# CNY70.net
KiCad netlist of a schematic drawn in EAGLE
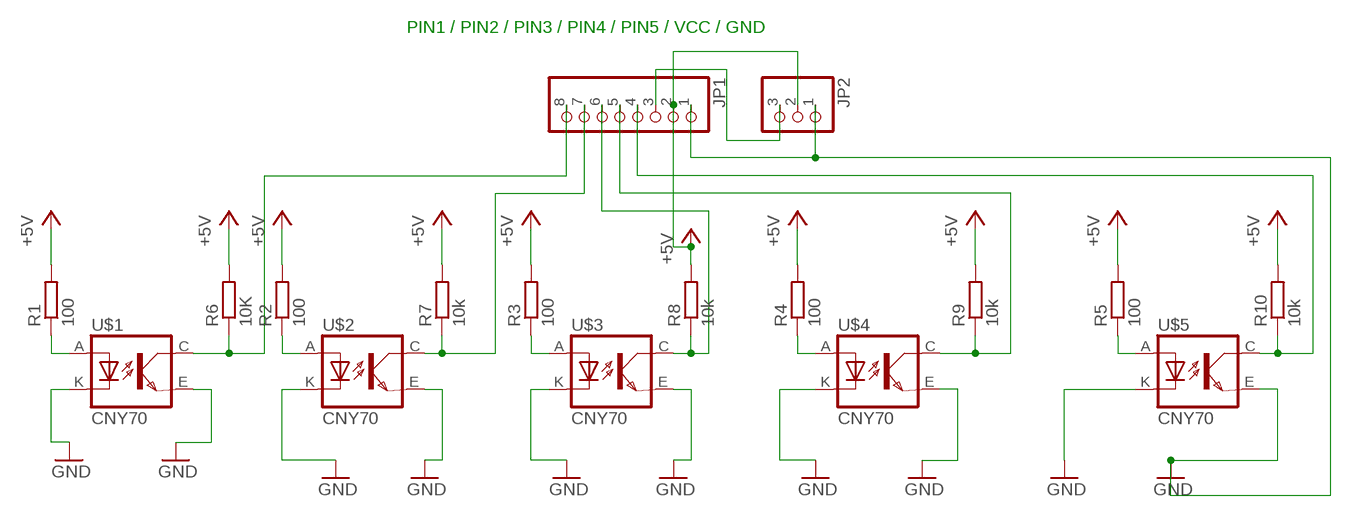
[diagram p0: schematic, sheet 1]

(export (version "E")
  (design (tool "Eeschema 10.0.6"))
  (components
    (comp (ref "JP1")
      (value "PINHD-1X8")
      (footprint "eagle-import:1X08")
      (libsource (lib "eagle-import") (part "PINHD-1X8"))
    )
    (comp (ref "JP2")
      (value "PINHD-1X3")
      (footprint "eagle-import:1X03")
      (libsource (lib "eagle-import") (part "PINHD-1X3"))
    )
    (comp (ref "R1")
      (value "100")
      (footprint "eagle-import:0309_12")
      (libsource (lib "eagle-import") (part "R-EU_0309/12"))
    )
    (comp (ref "R2")
      (value "100")
      (footprint "eagle-import:0309_12")
      (libsource (lib "eagle-import") (part "R-EU_0309/12"))
    )
    (comp (ref "R3")
      (value "100")
      (footprint "eagle-import:0309_12")
      (libsource (lib "eagle-import") (part "R-EU_0309/12"))
    )
    (comp (ref "R4")
      (value "100")
      (footprint "eagle-import:0309_12")
      (libsource (lib "eagle-import") (part "R-EU_0309/12"))
    )
    (comp (ref "R5")
      (value "100")
      (footprint "eagle-import:0309_12")
      (libsource (lib "eagle-import") (part "R-EU_0309/12"))
    )
    (comp (ref "R6")
      (value "10K")
      (footprint "eagle-import:0309_12")
      (libsource (lib "eagle-import") (part "R-EU_0309/12"))
    )
    (comp (ref "R7")
      (value "10k")
      (footprint "eagle-import:0309_12")
      (libsource (lib "eagle-import") (part "R-EU_0309/12"))
    )
    (comp (ref "R8")
      (value "10k")
      (footprint "eagle-import:0309_12")
      (libsource (lib "eagle-import") (part "R-EU_0309/12"))
    )
    (comp (ref "R9")
      (value "10k")
      (footprint "eagle-import:0309_12")
      (libsource (lib "eagle-import") (part "R-EU_0309/12"))
    )
    (comp (ref "R10")
      (value "10k")
      (footprint "eagle-import:0309_12")
      (libsource (lib "eagle-import") (part "R-EU_0309/12"))
    )
    (comp (ref "U$1")
      (value "CNY70")
      (footprint "eagle-import:4")
      (libsource (lib "eagle-import") (part "CNY70"))
    )
    (comp (ref "U$2")
      (value "CNY70")
      (footprint "eagle-import:4")
      (libsource (lib "eagle-import") (part "CNY70"))
    )
    (comp (ref "U$3")
      (value "CNY70")
      (footprint "eagle-import:4")
      (libsource (lib "eagle-import") (part "CNY70"))
    )
    (comp (ref "U$4")
      (value "CNY70")
      (footprint "eagle-import:4")
      (libsource (lib "eagle-import") (part "CNY70"))
    )
    (comp (ref "U$5")
      (value "CNY70")
      (footprint "eagle-import:4")
      (libsource (lib "eagle-import") (part "CNY70"))
    )
  )
  (nets
    (net (code "1") (name "+5V") (class "Default")
      (node (ref "JP1") (pin "2") (pinfunction "2_2") (pintype "passive"))
      (node (ref "JP2") (pin "2") (pinfunction "2_2") (pintype "passive"))
      (node (ref "R1") (pin "2") (pinfunction "2_2") (pintype "passive"))
      (node (ref "R10") (pin "2") (pinfunction "2_2") (pintype "passive"))
      (node (ref "R2") (pin "2") (pinfunction "2_2") (pintype "passive"))
      (node (ref "R3") (pin "2") (pinfunction "2_2") (pintype "passive"))
      (node (ref "R4") (pin "2") (pinfunction "2_2") (pintype "passive"))
      (node (ref "R5") (pin "2") (pinfunction "2_2") (pintype "passive"))
      (node (ref "R6") (pin "2") (pinfunction "2_2") (pintype "passive"))
      (node (ref "R7") (pin "2") (pinfunction "2_2") (pintype "passive"))
      (node (ref "R8") (pin "2") (pinfunction "2_2") (pintype "passive"))
      (node (ref "R9") (pin "2") (pinfunction "2_2") (pintype "passive"))
    )
    (net (code "2") (name "GND") (class "Default")
      (node (ref "JP1") (pin "1") (pinfunction "1_1") (pintype "passive"))
      (node (ref "JP2") (pin "1") (pinfunction "1_1") (pintype "passive"))
      (node (ref "U$1") (pin "E") (pinfunction "EMI_E") (pintype "passive"))
      (node (ref "U$1") (pin "K") (pinfunction "C_K") (pintype "passive"))
      (node (ref "U$2") (pin "E") (pinfunction "EMI_E") (pintype "passive"))
      (node (ref "U$2") (pin "K") (pinfunction "C_K") (pintype "passive"))
      (node (ref "U$3") (pin "E") (pinfunction "EMI_E") (pintype "passive"))
      (node (ref "U$3") (pin "K") (pinfunction "C_K") (pintype "passive"))
      (node (ref "U$4") (pin "E") (pinfunction "EMI_E") (pintype "passive"))
      (node (ref "U$4") (pin "K") (pinfunction "C_K") (pintype "passive"))
      (node (ref "U$5") (pin "E") (pinfunction "EMI_E") (pintype "passive"))
      (node (ref "U$5") (pin "K") (pinfunction "C_K") (pintype "passive"))
    )
    (net (code "3") (name "Net-(JP1-Pad3)") (class "Default")
      (node (ref "JP1") (pin "3") (pinfunction "3_3") (pintype "passive"))
      (node (ref "JP2") (pin "3") (pinfunction "3_3") (pintype "passive"))
    )
    (net (code "4") (name "Net-(R1-Pad1)") (class "Default")
      (node (ref "R1") (pin "1") (pinfunction "1_1") (pintype "passive"))
      (node (ref "U$1") (pin "A") (pinfunction "A_A") (pintype "passive"))
    )
    (net (code "5") (name "Net-(R2-Pad1)") (class "Default")
      (node (ref "R2") (pin "1") (pinfunction "1_1") (pintype "passive"))
      (node (ref "U$2") (pin "A") (pinfunction "A_A") (pintype "passive"))
    )
    (net (code "6") (name "Net-(R3-Pad1)") (class "Default")
      (node (ref "R3") (pin "1") (pinfunction "1_1") (pintype "passive"))
      (node (ref "U$3") (pin "A") (pinfunction "A_A") (pintype "passive"))
    )
    (net (code "7") (name "Net-(R4-Pad1)") (class "Default")
      (node (ref "R4") (pin "1") (pinfunction "1_1") (pintype "passive"))
      (node (ref "U$4") (pin "A") (pinfunction "A_A") (pintype "passive"))
    )
    (net (code "8") (name "Net-(R5-Pad1)") (class "Default")
      (node (ref "R5") (pin "1") (pinfunction "1_1") (pintype "passive"))
      (node (ref "U$5") (pin "A") (pinfunction "A_A") (pintype "passive"))
    )
    (net (code "9") (name "Net-(U$1-COL)") (class "Default")
      (node (ref "JP1") (pin "8") (pinfunction "8_8") (pintype "passive"))
      (node (ref "R6") (pin "1") (pinfunction "1_1") (pintype "passive"))
      (node (ref "U$1") (pin "C") (pinfunction "COL_C") (pintype "passive"))
    )
    (net (code "10") (name "Net-(U$2-COL)") (class "Default")
      (node (ref "JP1") (pin "7") (pinfunction "7_7") (pintype "passive"))
      (node (ref "R7") (pin "1") (pinfunction "1_1") (pintype "passive"))
      (node (ref "U$2") (pin "C") (pinfunction "COL_C") (pintype "passive"))
    )
    (net (code "11") (name "Net-(U$3-COL)") (class "Default")
      (node (ref "JP1") (pin "6") (pinfunction "6_6") (pintype "passive"))
      (node (ref "R8") (pin "1") (pinfunction "1_1") (pintype "passive"))
      (node (ref "U$3") (pin "C") (pinfunction "COL_C") (pintype "passive"))
    )
    (net (code "12") (name "Net-(U$4-COL)") (class "Default")
      (node (ref "JP1") (pin "5") (pinfunction "5_5") (pintype "passive"))
      (node (ref "R9") (pin "1") (pinfunction "1_1") (pintype "passive"))
      (node (ref "U$4") (pin "C") (pinfunction "COL_C") (pintype "passive"))
    )
    (net (code "13") (name "Net-(U$5-COL)") (class "Default")
      (node (ref "JP1") (pin "4") (pinfunction "4_4") (pintype "passive"))
      (node (ref "R10") (pin "1") (pinfunction "1_1") (pintype "passive"))
      (node (ref "U$5") (pin "C") (pinfunction "COL_C") (pintype "passive"))
    )
  )
)
